# Charger_18V-1_35A.net
KiCad netlist of a schematic drawn in EAGLE
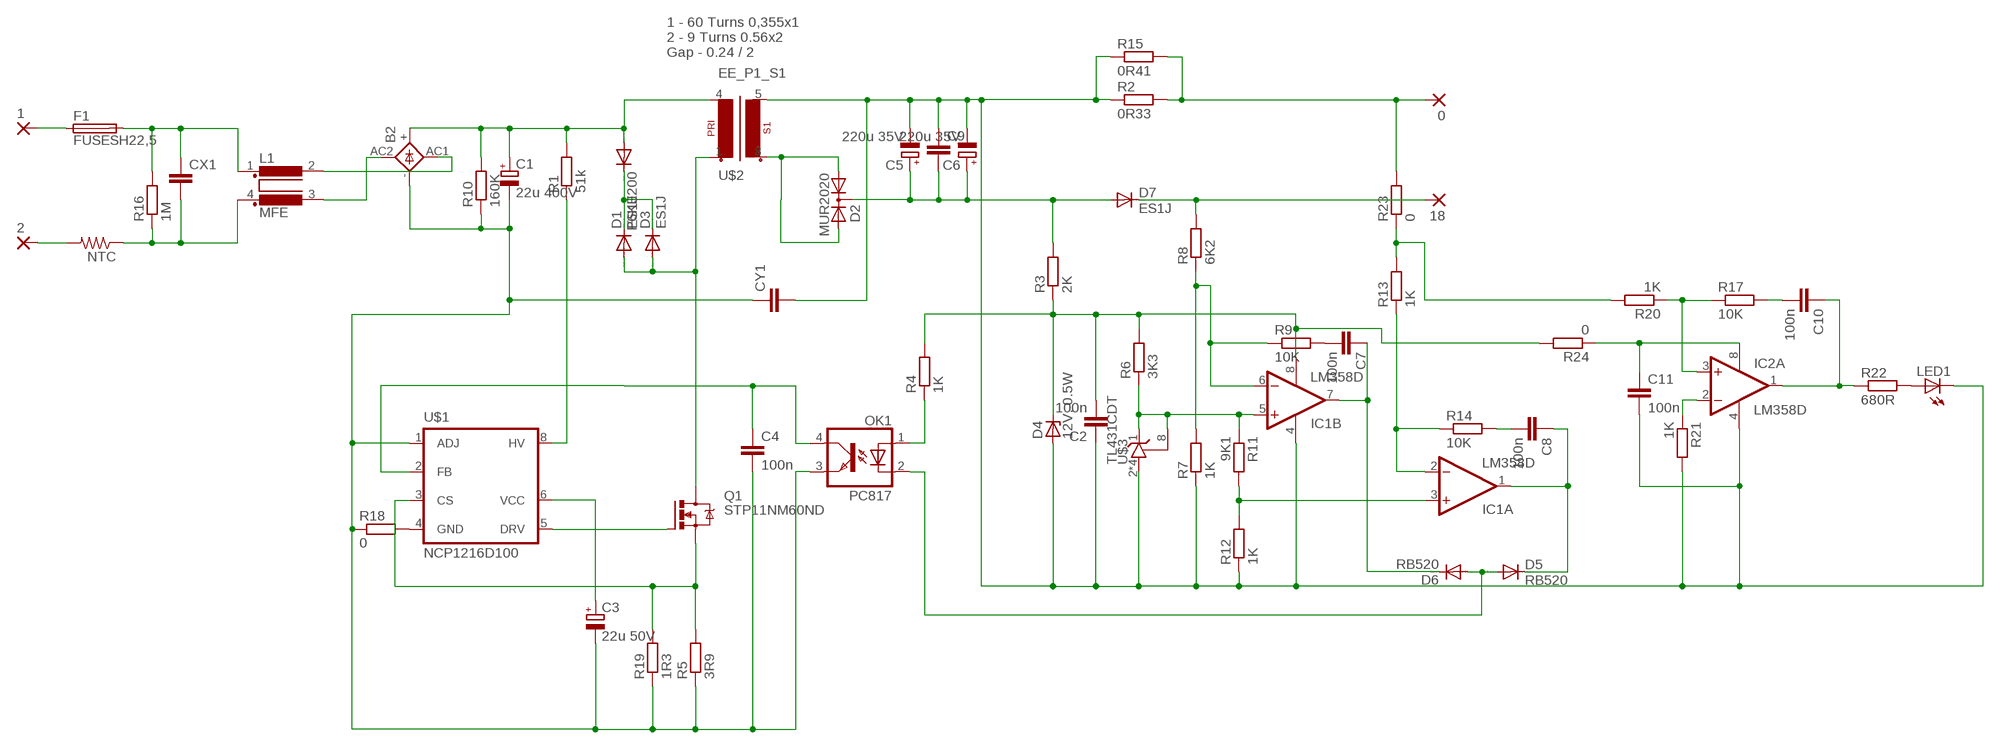
[diagram p0: schematic, sheet 1]

(export (version "E")
  (design (tool "Eeschema 10.0.6"))
  (components
    (comp (ref "0")
      (value "3,81/1,4")
      (footprint "eagle-import:3,81_1,4")
      (libsource (lib "eagle-import") (part "3,81/1,4"))
    )
    (comp (ref "1")
      (value "3,81/1,4")
      (footprint "eagle-import:3,81_1,4")
      (libsource (lib "eagle-import") (part "3,81/1,4"))
    )
    (comp (ref "2")
      (value "3,81/1,4")
      (footprint "eagle-import:3,81_1,4")
      (libsource (lib "eagle-import") (part "3,81/1,4"))
    )
    (comp (ref "18")
      (value "3,81/1,4")
      (footprint "eagle-import:3,81_1,4")
      (libsource (lib "eagle-import") (part "3,81/1,4"))
    )
    (comp (ref "B2")
      (value "RS-4M")
      (footprint "eagle-import:RS-4M")
      (libsource (lib "eagle-import") (part "RS-4M"))
    )
    (comp (ref "C1")
      (value "22u 400V")
      (footprint "eagle-import:E7,5-18")
      (libsource (lib "eagle-import") (part "CPOL-EUE7.5-18"))
    )
    (comp (ref "C2")
      (value "100n")
      (footprint "eagle-import:C0805")
      (libsource (lib "eagle-import") (part "C-EUC0805"))
    )
    (comp (ref "C3")
      (value "22u 50V")
      (footprint "eagle-import:E5-5")
      (libsource (lib "eagle-import") (part "CPOL-EUE5-5"))
    )
    (comp (ref "C4")
      (value "100n")
      (footprint "eagle-import:C0805")
      (libsource (lib "eagle-import") (part "C-EUC0805"))
    )
    (comp (ref "C5")
      (value "220u 35V")
      (footprint "eagle-import:E5-10,5")
      (libsource (lib "eagle-import") (part "CPOL-EUE5-10.5"))
    )
    (comp (ref "C6")
      (value "220u 35V")
      (footprint "eagle-import:E5-10,5")
      (libsource (lib "eagle-import") (part "CPOL-EUE5-10.5"))
    )
    (comp (ref "C7")
      (value "100n")
      (footprint "eagle-import:C0805")
      (libsource (lib "eagle-import") (part "C-EUC0805"))
    )
    (comp (ref "C8")
      (value "100n")
      (footprint "eagle-import:C0805")
      (libsource (lib "eagle-import") (part "C-EUC0805"))
    )
    (comp (ref "C9")
      (value "C-EU050-025X075")
      (footprint "eagle-import:C050-025X075")
      (libsource (lib "eagle-import") (part "C-EU050-025X075"))
    )
    (comp (ref "C10")
      (value "100n")
      (footprint "eagle-import:C0805")
      (libsource (lib "eagle-import") (part "C-EUC0805"))
    )
    (comp (ref "C11")
      (value "100n")
      (footprint "eagle-import:C0805")
      (libsource (lib "eagle-import") (part "C-EUC0805"))
    )
    (comp (ref "CX1")
      (value "CXXC22B7")
      (footprint "eagle-import:XC22B7")
      (libsource (lib "eagle-import") (part "CXXC22B7"))
    )
    (comp (ref "CY1")
      (value "CYYC10B4")
      (footprint "eagle-import:YC10B4")
      (libsource (lib "eagle-import") (part "CYYC10B4"))
    )
    (comp (ref "D1")
      (value "ES1J")
      (footprint "eagle-import:DO-214AC")
      (libsource (lib "eagle-import") (part "DIODE-DO-214AC"))
    )
    (comp (ref "D2")
      (value "MUR2020")
      (footprint "eagle-import:TO220ABS")
      (libsource (lib "eagle-import") (part "DIODE-2AC|CATO220V"))
    )
    (comp (ref "D3")
      (value "ES1J")
      (footprint "eagle-import:DO-214AC")
      (libsource (lib "eagle-import") (part "DIODE-DO-214AC"))
    )
    (comp (ref "D4")
      (value "12V, 0.5W")
      (footprint "eagle-import:SOD80C")
      (libsource (lib "eagle-import") (part "ZENER-DIODESOD80C"))
    )
    (comp (ref "D5")
      (value "RB520")
      (footprint "eagle-import:SOD523")
      (libsource (lib "eagle-import") (part "DIODE-SOD523"))
    )
    (comp (ref "D6")
      (value "RB520")
      (footprint "eagle-import:SOD523")
      (libsource (lib "eagle-import") (part "DIODE-SOD523"))
    )
    (comp (ref "D7")
      (value "ES1J")
      (footprint "eagle-import:DO-214AC")
      (libsource (lib "eagle-import") (part "DIODE-DO-214AC"))
    )
    (comp (ref "F1")
      (value "FUSESH22,5")
      (footprint "eagle-import:SH22,5")
      (libsource (lib "eagle-import") (part "FUSESH22,5"))
    )
    (comp (ref "IC1")
      (value "LM358D")
      (footprint "eagle-import:SO08")
      (libsource (lib "eagle-import") (part "LM358D"))
    )
    (comp (ref "IC2")
      (value "LM358D")
      (footprint "eagle-import:SO08")
      (libsource (lib "eagle-import") (part "LM358D"))
    )
    (comp (ref "L1")
      (value "MFE")
      (footprint "eagle-import:MFE")
      (libsource (lib "eagle-import") (part "MFE"))
    )
    (comp (ref "LED1")
      (value "LED5MM")
      (footprint "eagle-import:LED5MM")
      (libsource (lib "eagle-import") (part "LED5MM"))
    )
    (comp (ref "NTC")
      (value "R-US_0207/7")
      (footprint "eagle-import:0207_7")
      (libsource (lib "eagle-import") (part "R-US_0207/7"))
    )
    (comp (ref "OK1")
      (value "PC817")
      (footprint "eagle-import:DIL04")
      (fields (field (name "MPN") "PC817X4J000F"))
      (libsource (lib "eagle-import") (part "PC817"))
    )
    (comp (ref "P6KE200")
      (value "DIODE-SMB")
      (footprint "eagle-import:SMB")
      (libsource (lib "eagle-import") (part "DIODE-SMB"))
    )
    (comp (ref "Q1")
      (value "STP11NM60ND")
      (footprint "eagle-import:TO220BV")
      (libsource (lib "eagle-import") (part "IRF740"))
    )
    (comp (ref "R1")
      (value "51k")
      (footprint "eagle-import:SQP-5")
      (libsource (lib "eagle-import") (part "R_SQP-5"))
    )
    (comp (ref "R2")
      (value "0R33")
      (footprint "eagle-import:0411_15")
      (libsource (lib "eagle-import") (part "R-EU_0411/15"))
    )
    (comp (ref "R3")
      (value "2K")
      (footprint "eagle-import:R1206")
      (libsource (lib "eagle-import") (part "R-EU_R1206"))
    )
    (comp (ref "R4")
      (value "1K")
      (footprint "eagle-import:R0603")
      (libsource (lib "eagle-import") (part "R-EU_R0603"))
    )
    (comp (ref "R5")
      (value "3R9")
      (footprint "eagle-import:0309_12")
      (libsource (lib "eagle-import") (part "R-EU_0309/12"))
    )
    (comp (ref "R6")
      (value "3K3")
      (footprint "eagle-import:R1206")
      (libsource (lib "eagle-import") (part "R-EU_R1206"))
    )
    (comp (ref "R7")
      (value "1K")
      (footprint "eagle-import:R0603")
      (libsource (lib "eagle-import") (part "R-EU_R0603"))
    )
    (comp (ref "R8")
      (value "6K2")
      (footprint "eagle-import:R0805")
      (libsource (lib "eagle-import") (part "R-EU_R0805"))
    )
    (comp (ref "R9")
      (value "10K")
      (footprint "eagle-import:R0805")
      (libsource (lib "eagle-import") (part "R-EU_R0805"))
    )
    (comp (ref "R10")
      (value "160K")
      (footprint "eagle-import:0204_7")
      (libsource (lib "eagle-import") (part "R-EU_0204/7"))
    )
    (comp (ref "R11")
      (value "9K1")
      (footprint "eagle-import:R1206")
      (libsource (lib "eagle-import") (part "R-EU_R1206"))
    )
    (comp (ref "R12")
      (value "1K")
      (footprint "eagle-import:R0603")
      (libsource (lib "eagle-import") (part "R-EU_R0603"))
    )
    (comp (ref "R13")
      (value "1K")
      (footprint "eagle-import:R0603")
      (libsource (lib "eagle-import") (part "R-EU_R0603"))
    )
    (comp (ref "R14")
      (value "10K")
      (footprint "eagle-import:R0805")
      (libsource (lib "eagle-import") (part "R-EU_R0805"))
    )
    (comp (ref "R15")
      (value "0R41")
      (footprint "eagle-import:0411_15")
      (libsource (lib "eagle-import") (part "R-EU_0411/15"))
    )
    (comp (ref "R16")
      (value "1M")
      (footprint "eagle-import:0207_12")
      (libsource (lib "eagle-import") (part "R-EU_0207/12"))
    )
    (comp (ref "R17")
      (value "10K")
      (footprint "eagle-import:R0805")
      (libsource (lib "eagle-import") (part "R-EU_R0805"))
    )
    (comp (ref "R18")
      (value "0")
      (footprint "eagle-import:R1206")
      (libsource (lib "eagle-import") (part "R-EU_R1206"))
    )
    (comp (ref "R19")
      (value "1R3")
      (footprint "eagle-import:0309_12")
      (libsource (lib "eagle-import") (part "R-EU_0309/12"))
    )
    (comp (ref "R20")
      (value "1K")
      (footprint "eagle-import:R0603")
      (libsource (lib "eagle-import") (part "R-EU_R0603"))
    )
    (comp (ref "R21")
      (value "1K")
      (footprint "eagle-import:R0603")
      (libsource (lib "eagle-import") (part "R-EU_R0603"))
    )
    (comp (ref "R22")
      (value "680R")
      (footprint "eagle-import:R0805")
      (libsource (lib "eagle-import") (part "R-EU_R0805"))
    )
    (comp (ref "R23")
      (value "0")
      (footprint "eagle-import:R1206")
      (libsource (lib "eagle-import") (part "R-EU_R1206"))
    )
    (comp (ref "R24")
      (value "0")
      (footprint "eagle-import:R1206")
      (libsource (lib "eagle-import") (part "R-EU_R1206"))
    )
    (comp (ref "U$1")
      (value "NCP1216D100")
      (footprint "eagle-import:SOP8")
      (libsource (lib "eagle-import") (part "NCP1200-100SO"))
    )
    (comp (ref "U$2")
      (value "EE_P1_S1")
      (footprint "eagle-import:EE25_P1_S1")
      (libsource (lib "eagle-import") (part "EE_P1_S1"))
    )
    (comp (ref "U$3")
      (value "TL431CDT")
      (footprint "eagle-import:SO8")
      (libsource (lib "eagle-import") (part "TL431CDT"))
    )
  )
  (nets
    (net (code "1") (name "Net-(0-P)") (class "Default")
      (node (ref "0") (pin "1") (pinfunction "P_1") (pintype "passive"))
      (node (ref "R15") (pin "2") (pinfunction "2_2") (pintype "passive"))
      (node (ref "R2") (pin "2") (pinfunction "2_2") (pintype "passive"))
      (node (ref "R23") (pin "2") (pinfunction "2_2") (pintype "passive"))
    )
    (net (code "2") (name "Net-(1-P)") (class "Default")
      (node (ref "1") (pin "1") (pinfunction "P_1") (pintype "passive"))
      (node (ref "F1") (pin "1") (pinfunction "1_1") (pintype "passive"))
    )
    (net (code "3") (name "Net-(2-P)") (class "Default")
      (node (ref "2") (pin "1") (pinfunction "P_1") (pintype "passive"))
      (node (ref "NTC") (pin "2") (pinfunction "2_2") (pintype "passive"))
    )
    (net (code "4") (name "Net-(18-P)") (class "Default")
      (node (ref "18") (pin "1") (pinfunction "P_1") (pintype "passive"))
      (node (ref "D7") (pin "C") (pinfunction "C_C") (pintype "passive"))
      (node (ref "R8") (pin "2") (pinfunction "2_2") (pintype "passive"))
    )
    (net (code "5") (name "Net-(B2-AC1)") (class "Default")
      (node (ref "B2") (pin "AC2") (pinfunction "AC1_AC2") (pintype "passive"))
      (node (ref "L1") (pin "3") (pinfunction "4_3") (pintype "passive"))
    )
    (net (code "6") (name "Net-(B2-AC2)") (class "Default")
      (node (ref "B2") (pin "AC1") (pinfunction "AC2_AC1") (pintype "passive"))
      (node (ref "L1") (pin "2") (pinfunction "2_2") (pintype "passive"))
    )
    (net (code "7") (name "Net-(C5-Pad+)") (class "Default")
      (node (ref "C5") (pin "+") (pinfunction "+_+") (pintype "passive"))
      (node (ref "C6") (pin "+") (pinfunction "+_+") (pintype "passive"))
      (node (ref "C9") (pin "2") (pinfunction "2_2") (pintype "passive"))
      (node (ref "D2") (pin "C") (pinfunction "C_C") (pintype "passive"))
      (node (ref "D7") (pin "A") (pinfunction "A_A") (pintype "passive"))
      (node (ref "R3") (pin "2") (pinfunction "2_2") (pintype "passive"))
    )
    (net (code "8") (name "Net-(C7-Pad2)") (class "Default")
      (node (ref "C7") (pin "2") (pinfunction "2_2") (pintype "passive"))
      (node (ref "R9") (pin "2") (pinfunction "2_2") (pintype "passive"))
    )
    (net (code "9") (name "Net-(C8-Pad2)") (class "Default")
      (node (ref "C8") (pin "2") (pinfunction "2_2") (pintype "passive"))
      (node (ref "R14") (pin "2") (pinfunction "2_2") (pintype "passive"))
    )
    (net (code "10") (name "Net-(C10-Pad2)") (class "Default")
      (node (ref "C10") (pin "2") (pinfunction "2_2") (pintype "passive"))
      (node (ref "R17") (pin "2") (pinfunction "2_2") (pintype "passive"))
    )
    (net (code "11") (name "Net-(CX1-Pad1)") (class "Default")
      (node (ref "CX1") (pin "1") (pinfunction "1_1") (pintype "passive"))
      (node (ref "F1") (pin "2") (pinfunction "2_2") (pintype "passive"))
      (node (ref "L1") (pin "1") (pinfunction "1_1") (pintype "passive"))
      (node (ref "R16") (pin "2") (pinfunction "2_2") (pintype "passive"))
    )
    (net (code "12") (name "Net-(D1-PadC)") (class "Default")
      (node (ref "D1") (pin "C") (pinfunction "C_C") (pintype "passive"))
      (node (ref "D3") (pin "C") (pinfunction "C_C") (pintype "passive"))
      (node (ref "P6KE200") (pin "C") (pinfunction "C_C") (pintype "passive"))
    )
    (net (code "13") (name "Net-(IC1A-+IN)") (class "Default")
      (node (ref "IC1") (pin "3") (pinfunction "+IN_3") (pintype "input"))
      (node (ref "R11") (pin "2") (pinfunction "2_2") (pintype "passive"))
      (node (ref "R12") (pin "2") (pinfunction "2_2") (pintype "passive"))
    )
    (net (code "14") (name "Net-(IC1A--IN)") (class "Default")
      (node (ref "IC1") (pin "2") (pinfunction "-IN_2") (pintype "input"))
      (node (ref "R13") (pin "1") (pinfunction "1_1") (pintype "passive"))
      (node (ref "R14") (pin "1") (pinfunction "1_1") (pintype "passive"))
    )
    (net (code "15") (name "Net-(IC1A-OUT)") (class "Default")
      (node (ref "C8") (pin "1") (pinfunction "1_1") (pintype "passive"))
      (node (ref "D5") (pin "C") (pinfunction "C_C") (pintype "passive"))
      (node (ref "IC1") (pin "1") (pinfunction "OUT_1") (pintype "output"))
    )
    (net (code "16") (name "Net-(IC1B-+IN)") (class "Default")
      (node (ref "IC1") (pin "5") (pinfunction "+IN_5") (pintype "input"))
      (node (ref "R11") (pin "1") (pinfunction "1_1") (pintype "passive"))
      (node (ref "R6") (pin "1") (pinfunction "1_1") (pintype "passive"))
      (node (ref "U$3") (pin "1") (pinfunction "C_1") (pintype "passive"))
      (node (ref "U$3") (pin "8") (pinfunction "R_8") (pintype "passive"))
    )
    (net (code "17") (name "Net-(IC1B--IN)") (class "Default")
      (node (ref "IC1") (pin "6") (pinfunction "-IN_6") (pintype "input"))
      (node (ref "R7") (pin "2") (pinfunction "2_2") (pintype "passive"))
      (node (ref "R8") (pin "1") (pinfunction "1_1") (pintype "passive"))
      (node (ref "R9") (pin "1") (pinfunction "1_1") (pintype "passive"))
    )
    (net (code "18") (name "Net-(IC1B-OUT)") (class "Default")
      (node (ref "C7") (pin "1") (pinfunction "1_1") (pintype "passive"))
      (node (ref "D6") (pin "C") (pinfunction "C_C") (pintype "passive"))
      (node (ref "IC1") (pin "7") (pinfunction "OUT_7") (pintype "output"))
    )
    (net (code "19") (name "Net-(IC1C-V+)") (class "Default")
      (node (ref "C2") (pin "2") (pinfunction "2_2") (pintype "passive"))
      (node (ref "D4") (pin "C") (pinfunction "C_C") (pintype "passive"))
      (node (ref "IC1") (pin "8") (pinfunction "V+_8") (pintype "power_in"))
      (node (ref "R24") (pin "2") (pinfunction "2_2") (pintype "passive"))
      (node (ref "R3") (pin "1") (pinfunction "1_1") (pintype "passive"))
      (node (ref "R4") (pin "2") (pinfunction "2_2") (pintype "passive"))
      (node (ref "R6") (pin "2") (pinfunction "2_2") (pintype "passive"))
    )
    (net (code "20") (name "Net-(IC1C-V-)") (class "Default")
      (node (ref "C11") (pin "2") (pinfunction "2_2") (pintype "passive"))
      (node (ref "C2") (pin "1") (pinfunction "1_1") (pintype "passive"))
      (node (ref "C5") (pin "-") (pinfunction "-_-") (pintype "passive"))
      (node (ref "C6") (pin "-") (pinfunction "-_-") (pintype "passive"))
      (node (ref "C9") (pin "1") (pinfunction "1_1") (pintype "passive"))
      (node (ref "CY1") (pin "2") (pinfunction "2_2") (pintype "passive"))
      (node (ref "D4") (pin "A") (pinfunction "A_A") (pintype "passive"))
      (node (ref "IC1") (pin "4") (pinfunction "V-_4") (pintype "power_in"))
      (node (ref "IC2") (pin "4") (pinfunction "V-_4") (pintype "power_in"))
      (node (ref "LED1") (pin "K") (pinfunction "C_K") (pintype "passive"))
      (node (ref "R12") (pin "1") (pinfunction "1_1") (pintype "passive"))
      (node (ref "R15") (pin "1") (pinfunction "1_1") (pintype "passive"))
      (node (ref "R2") (pin "1") (pinfunction "1_1") (pintype "passive"))
      (node (ref "R21") (pin "2") (pinfunction "2_2") (pintype "passive"))
      (node (ref "R7") (pin "1") (pinfunction "1_1") (pintype "passive"))
      (node (ref "U$2") (pin "5") (pinfunction "S1-2_5") (pintype "passive"))
      (node (ref "U$3") (pin "2") (pinfunction "A_2") (pintype "passive"))
      (node (ref "U$3") (pin "3") (pinfunction "A_3") (pintype "passive"))
      (node (ref "U$3") (pin "6") (pinfunction "A_6") (pintype "passive"))
      (node (ref "U$3") (pin "7") (pinfunction "A_7") (pintype "passive"))
    )
    (net (code "21") (name "Net-(IC2A-+IN)") (class "Default")
      (node (ref "IC2") (pin "3") (pinfunction "+IN_3") (pintype "input"))
      (node (ref "R17") (pin "1") (pinfunction "1_1") (pintype "passive"))
      (node (ref "R20") (pin "1") (pinfunction "1_1") (pintype "passive"))
    )
    (net (code "22") (name "Net-(IC2A--IN)") (class "Default")
      (node (ref "IC2") (pin "2") (pinfunction "-IN_2") (pintype "input"))
      (node (ref "R21") (pin "1") (pinfunction "1_1") (pintype "passive"))
    )
    (net (code "23") (name "Net-(IC2A-OUT)") (class "Default")
      (node (ref "C10") (pin "1") (pinfunction "1_1") (pintype "passive"))
      (node (ref "IC2") (pin "1") (pinfunction "OUT_1") (pintype "output"))
      (node (ref "R22") (pin "1") (pinfunction "1_1") (pintype "passive"))
    )
    (net (code "24") (name "Net-(IC2C-V+)") (class "Default")
      (node (ref "C11") (pin "1") (pinfunction "1_1") (pintype "passive"))
      (node (ref "IC2") (pin "8") (pinfunction "V+_8") (pintype "power_in"))
      (node (ref "R24") (pin "1") (pinfunction "1_1") (pintype "passive"))
    )
    (net (code "25") (name "Net-(L1-3)") (class "Default")
      (node (ref "CX1") (pin "2") (pinfunction "2_2") (pintype "passive"))
      (node (ref "L1") (pin "4") (pinfunction "3_4") (pintype "passive"))
      (node (ref "NTC") (pin "1") (pinfunction "1_1") (pintype "passive"))
      (node (ref "R16") (pin "1") (pinfunction "1_1") (pintype "passive"))
    )
    (net (code "26") (name "Net-(LED1-PadA)") (class "Default")
      (node (ref "LED1") (pin "A") (pinfunction "A_A") (pintype "passive"))
      (node (ref "R22") (pin "2") (pinfunction "2_2") (pintype "passive"))
    )
    (net (code "27") (name "Net-(OK1-A)") (class "Default")
      (node (ref "OK1") (pin "1") (pinfunction "A_1") (pintype "passive"))
      (node (ref "R4") (pin "1") (pinfunction "1_1") (pintype "passive"))
    )
    (net (code "28") (name "Net-(OK1-C)") (class "Default")
      (node (ref "D5") (pin "A") (pinfunction "A_A") (pintype "passive"))
      (node (ref "D6") (pin "A") (pinfunction "A_A") (pintype "passive"))
      (node (ref "OK1") (pin "2") (pinfunction "C_2") (pintype "passive"))
    )
    (net (code "29") (name "Net-(OK1-COL)") (class "Default")
      (node (ref "C4") (pin "1") (pinfunction "1_1") (pintype "passive"))
      (node (ref "OK1") (pin "4") (pinfunction "COL_4") (pintype "passive"))
      (node (ref "U$1") (pin "2") (pinfunction "FB_2") (pintype "input"))
    )
    (net (code "30") (name "Net-(OK1-EMIT)") (class "Default")
      (node (ref "B2") (pin "-") (pinfunction "-_-") (pintype "passive"))
      (node (ref "C1") (pin "-") (pinfunction "-_-") (pintype "passive"))
      (node (ref "C3") (pin "-") (pinfunction "-_-") (pintype "passive"))
      (node (ref "C4") (pin "2") (pinfunction "2_2") (pintype "passive"))
      (node (ref "CY1") (pin "1") (pinfunction "1_1") (pintype "passive"))
      (node (ref "OK1") (pin "3") (pinfunction "EMIT_3") (pintype "passive"))
      (node (ref "R10") (pin "1") (pinfunction "1_1") (pintype "passive"))
      (node (ref "R18") (pin "1") (pinfunction "1_1") (pintype "passive"))
      (node (ref "R19") (pin "1") (pinfunction "1_1") (pintype "passive"))
      (node (ref "R5") (pin "1") (pinfunction "1_1") (pintype "passive"))
      (node (ref "U$1") (pin "1") (pinfunction "ADJ_1") (pintype "passive"))
    )
    (net (code "31") (name "Net-(R13-Pad2)") (class "Default")
      (node (ref "R13") (pin "2") (pinfunction "2_2") (pintype "passive"))
      (node (ref "R20") (pin "2") (pinfunction "2_2") (pintype "passive"))
      (node (ref "R23") (pin "1") (pinfunction "1_1") (pintype "passive"))
    )
    (net (code "32") (name "Net-(U$1-CS)") (class "Default")
      (node (ref "Q1") (pin "S") (pinfunction "S_S") (pintype "passive"))
      (node (ref "R19") (pin "2") (pinfunction "2_2") (pintype "passive"))
      (node (ref "R5") (pin "2") (pinfunction "2_2") (pintype "passive"))
      (node (ref "U$1") (pin "3") (pinfunction "CS_3") (pintype "input"))
    )
    (net (code "33") (name "Net-(U$1-DRV)") (class "Default")
      (node (ref "Q1") (pin "G") (pinfunction "G_G") (pintype "passive"))
      (node (ref "U$1") (pin "5") (pinfunction "DRV_5") (pintype "power_in"))
    )
    (net (code "34") (name "Net-(U$1-GND)") (class "Default")
      (node (ref "R18") (pin "2") (pinfunction "2_2") (pintype "passive"))
      (node (ref "U$1") (pin "4") (pinfunction "GND_4") (pintype "passive"))
    )
    (net (code "35") (name "Net-(U$1-HV)") (class "Default")
      (node (ref "R1") (pin "1") (pinfunction "1_1") (pintype "passive"))
      (node (ref "U$1") (pin "8") (pinfunction "HV_8") (pintype "passive"))
    )
    (net (code "36") (name "Net-(U$1-VCC)") (class "Default")
      (node (ref "C3") (pin "+") (pinfunction "+_+") (pintype "passive"))
      (node (ref "U$1") (pin "6") (pinfunction "VCC_6") (pintype "output"))
    )
    (net (code "37") (name "Net-(U$2-P1-1)") (class "Default")
      (node (ref "D1") (pin "A") (pinfunction "A_A") (pintype "passive"))
      (node (ref "D3") (pin "A") (pinfunction "A_A") (pintype "passive"))
      (node (ref "Q1") (pin "D") (pinfunction "D_D") (pintype "passive"))
      (node (ref "U$2") (pin "1") (pinfunction "P1-1_1") (pintype "passive"))
    )
    (net (code "38") (name "Net-(U$2-P1-2)") (class "Default")
      (node (ref "B2") (pin "+") (pinfunction "+_+") (pintype "passive"))
      (node (ref "C1") (pin "+") (pinfunction "+_+") (pintype "passive"))
      (node (ref "P6KE200") (pin "A") (pinfunction "A_A") (pintype "passive"))
      (node (ref "R1") (pin "2") (pinfunction "2_2") (pintype "passive"))
      (node (ref "R10") (pin "2") (pinfunction "2_2") (pintype "passive"))
      (node (ref "U$2") (pin "4") (pinfunction "P1-2_4") (pintype "passive"))
    )
    (net (code "39") (name "Net-(U$2-S1-1)") (class "Default")
      (node (ref "D2") (pin "A1") (pinfunction "A1_A1") (pintype "passive"))
      (node (ref "D2") (pin "A2") (pinfunction "A2_A2") (pintype "passive"))
      (node (ref "U$2") (pin "8") (pinfunction "S1-1_8") (pintype "passive"))
    )
  )
)
